# SimpleSimon.net
KiCad netlist of a schematic drawn in EAGLE
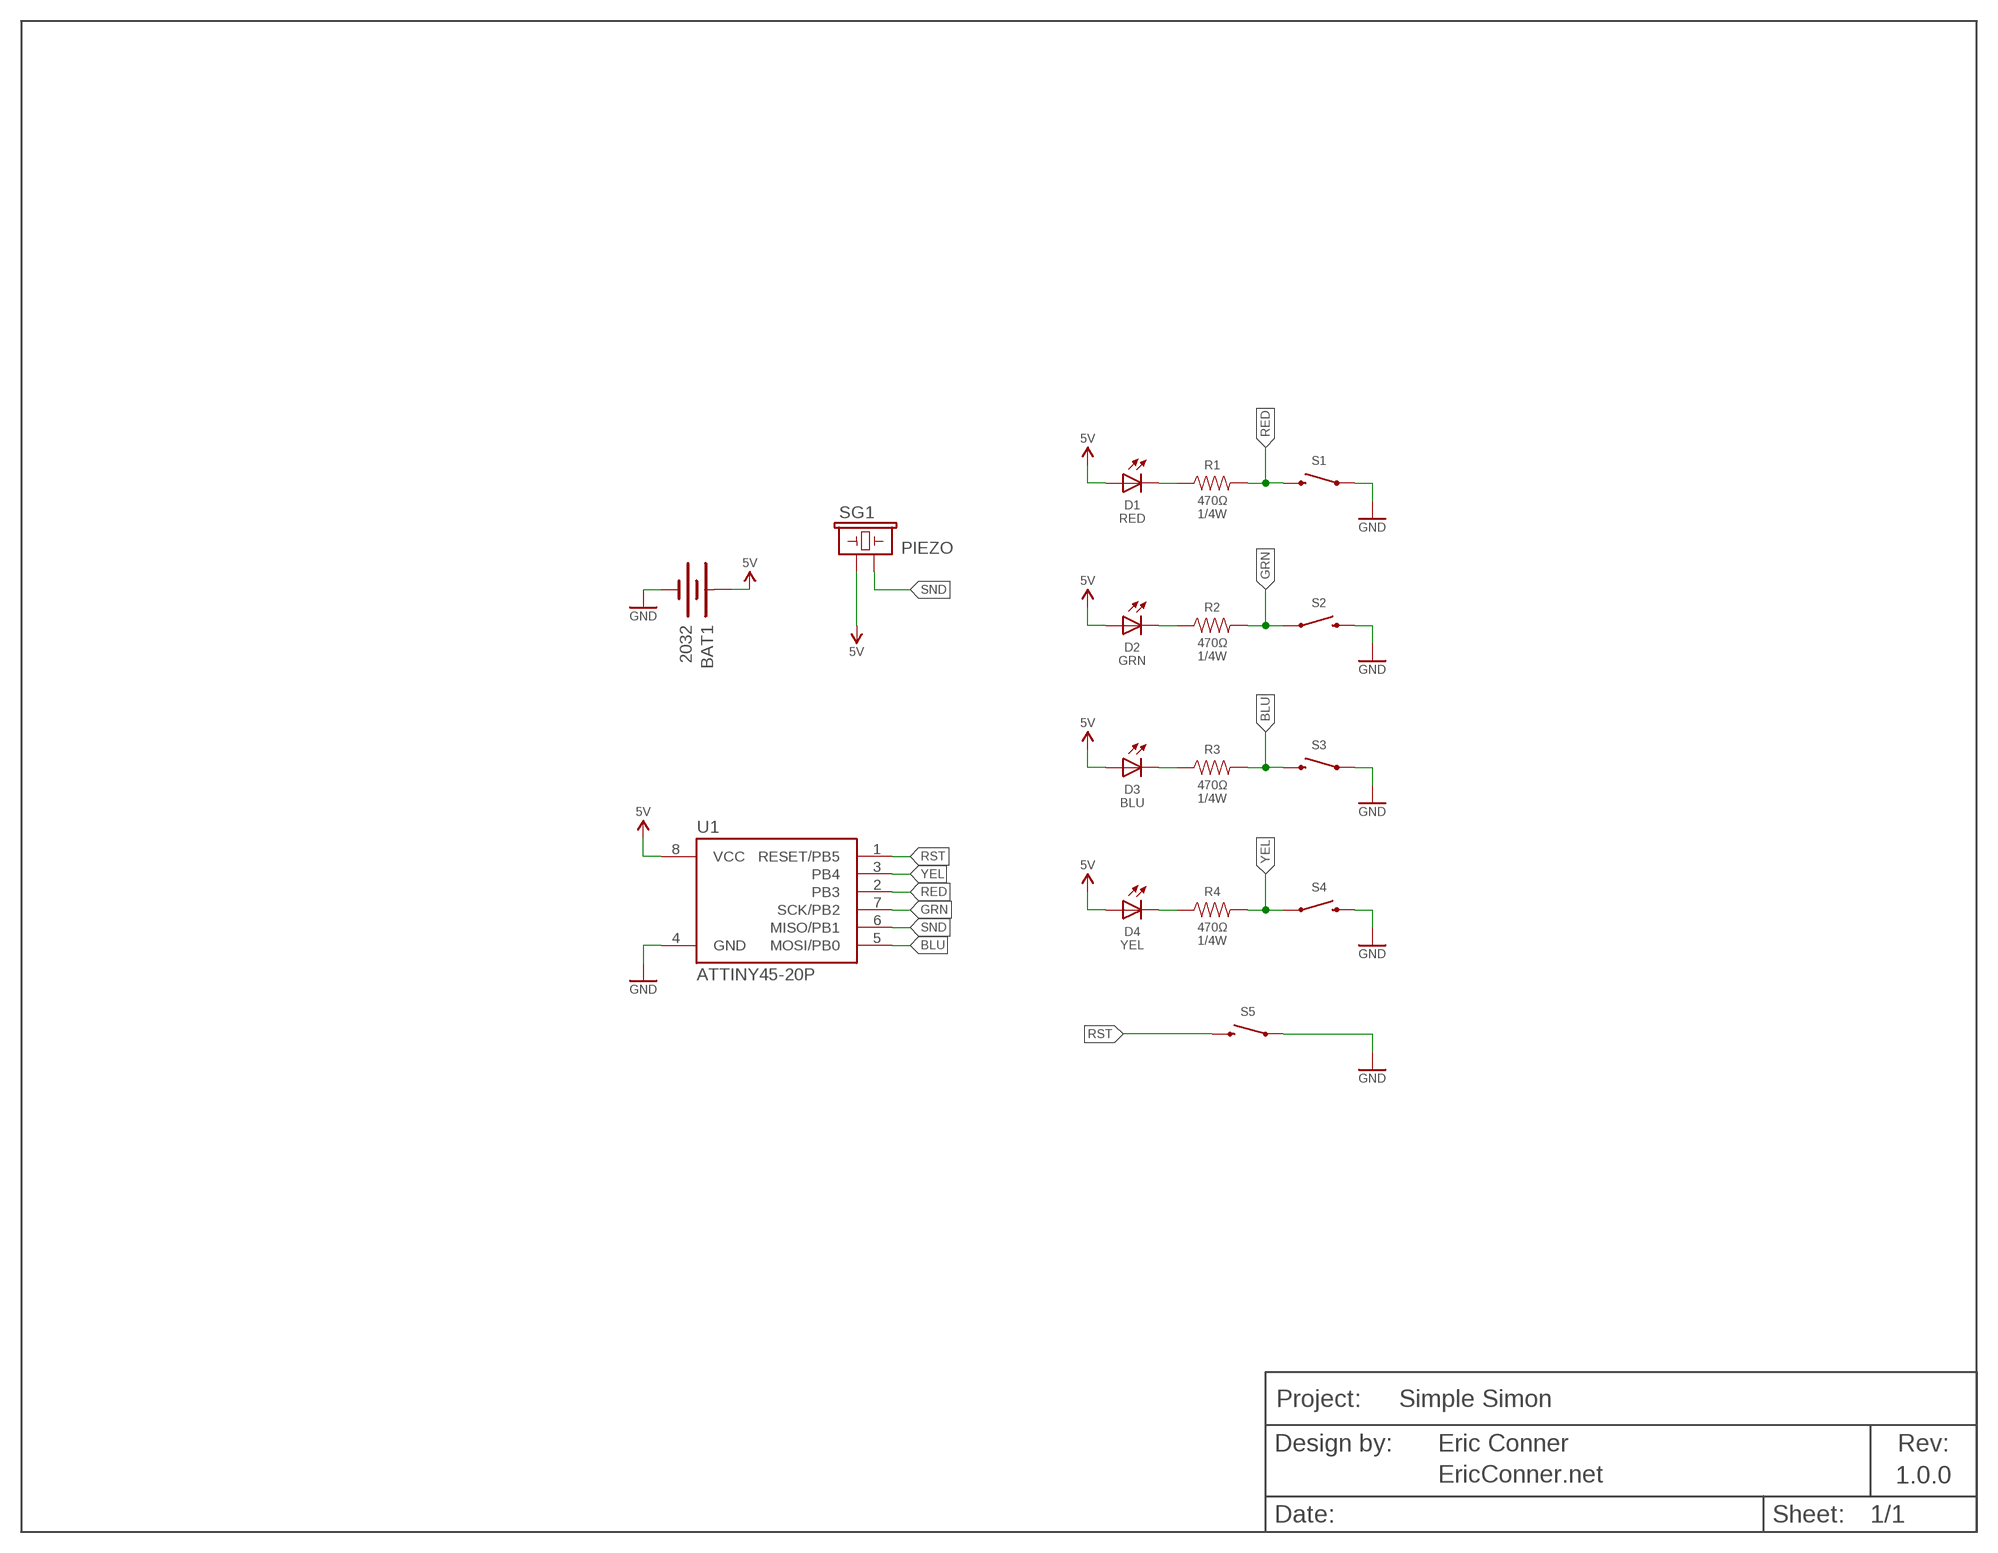
[diagram p0: schematic, sheet 1]

(export (version "E")
  (design (tool "Eeschema 10.0.6"))
  (components
    (comp (ref "BAT1")
      (value "2032")
      (footprint "eagle-import:BAT-2032")
      (libsource (lib "eagle-import") (part "BATTERY2032"))
    )
    (comp (ref "BORDER1")
      (value "BORDER_LETTER-MINIMAL")
      (footprint "eagle-import:MINIMAL_LOGO")
      (fields
        (field (name "PROJECT") "Simple Simon")
        (field (name "DESIGNER") "Eric Conner")
        (field (name "VERSION") "1.0.0")
        (field (name "WEBSITE") "EricConner.net")
        (field (name "PROJECT_1") "Simple Simon")
      )
      (libsource (lib "eagle-import") (part "BORDER_LETTER-MINIMAL"))
    )
    (comp (ref "D1")
      (value "RED")
      (footprint "eagle-import:LED5MM")
      (libsource (lib "eagle-import") (part "LED5MM"))
    )
    (comp (ref "D2")
      (value "GRN")
      (footprint "eagle-import:LED5MM")
      (libsource (lib "eagle-import") (part "LED5MM"))
    )
    (comp (ref "D3")
      (value "BLU")
      (footprint "eagle-import:LED5MM")
      (libsource (lib "eagle-import") (part "LED5MM"))
    )
    (comp (ref "D4")
      (value "YEL")
      (footprint "eagle-import:LED5MM")
      (libsource (lib "eagle-import") (part "LED5MM"))
    )
    (comp (ref "R1")
      (value "470Ω")
      (footprint "eagle-import:1_4R")
      (fields (field (name "ATTRIBUTE") "1/4W") (field (name "DIGIKEY") "CF14JT470RCT-ND"))
      (libsource (lib "eagle-import") (part "RESISTOR1/4W"))
    )
    (comp (ref "R2")
      (value "470Ω")
      (footprint "eagle-import:1_4R")
      (fields (field (name "ATTRIBUTE") "1/4W") (field (name "DIGIKEY") "CF14JT470RCT-ND"))
      (libsource (lib "eagle-import") (part "RESISTOR1/4W"))
    )
    (comp (ref "R3")
      (value "470Ω")
      (footprint "eagle-import:1_4R")
      (fields (field (name "ATTRIBUTE") "1/4W") (field (name "DIGIKEY") "CF14JT470RCT-ND"))
      (libsource (lib "eagle-import") (part "RESISTOR1/4W"))
    )
    (comp (ref "R4")
      (value "470Ω")
      (footprint "eagle-import:1_4R")
      (fields (field (name "ATTRIBUTE") "1/4W") (field (name "DIGIKEY") "CF14JT470RCT-ND"))
      (libsource (lib "eagle-import") (part "RESISTOR1/4W"))
    )
    (comp (ref "S1")
      (value "SWITCH-MOMENTARY-2PTH")
      (footprint "eagle-import:TACTILE-PTH")
      (libsource (lib "eagle-import") (part "SWITCH-MOMENTARY-2PTH"))
    )
    (comp (ref "S2")
      (value "SWITCH-MOMENTARY-2PTH")
      (footprint "eagle-import:TACTILE-PTH")
      (libsource (lib "eagle-import") (part "SWITCH-MOMENTARY-2PTH"))
    )
    (comp (ref "S3")
      (value "SWITCH-MOMENTARY-2PTH")
      (footprint "eagle-import:TACTILE-PTH")
      (libsource (lib "eagle-import") (part "SWITCH-MOMENTARY-2PTH"))
    )
    (comp (ref "S4")
      (value "SWITCH-MOMENTARY-2PTH")
      (footprint "eagle-import:TACTILE-PTH")
      (libsource (lib "eagle-import") (part "SWITCH-MOMENTARY-2PTH"))
    )
    (comp (ref "S5")
      (value "SWITCH-MOMENTARY-2PTH")
      (footprint "eagle-import:TACTILE-PTH")
      (libsource (lib "eagle-import") (part "SWITCH-MOMENTARY-2PTH"))
    )
    (comp (ref "SG1")
      (value "PIEZO")
      (footprint "eagle-import:BUZZER-12MM")
      (libsource (lib "eagle-import") (part "BUZZERPTH"))
    )
    (comp (ref "U1")
      (value "ATTINY45-20P")
      (footprint "eagle-import:PDIP08_300MIL")
      (libsource (lib "eagle-import") (part "ATTINY45P-20"))
    )
  )
  (nets
    (net (code "1") (name "5V") (class "Default")
      (node (ref "BAT1") (pin "+") (pinfunction "+_+") (pintype "power_in"))
      (node (ref "D1") (pin "A") (pinfunction "A_A") (pintype "passive"))
      (node (ref "D2") (pin "A") (pinfunction "A_A") (pintype "passive"))
      (node (ref "D3") (pin "A") (pinfunction "A_A") (pintype "passive"))
      (node (ref "D4") (pin "A") (pinfunction "A_A") (pintype "passive"))
      (node (ref "SG1") (pin "+") (pinfunction "1_+") (pintype "passive"))
      (node (ref "U1") (pin "8") (pinfunction "VCC_8") (pintype "power_in"))
    )
    (net (code "2") (name "BLU") (class "Default")
      (node (ref "R3") (pin "P$2") (pinfunction "2_P$2") (pintype "passive"))
      (node (ref "S3") (pin "3") (pinfunction "2_3") (pintype "passive"))
      (node (ref "U1") (pin "5") (pinfunction "MOSI/PB0_5") (pintype "bidirectional"))
    )
    (net (code "3") (name "GND") (class "Default")
      (node (ref "BAT1") (pin "-") (pinfunction "-_-") (pintype "power_in"))
      (node (ref "S1") (pin "1") (pinfunction "1_1") (pintype "passive"))
      (node (ref "S2") (pin "3") (pinfunction "2_3") (pintype "passive"))
      (node (ref "S3") (pin "1") (pinfunction "1_1") (pintype "passive"))
      (node (ref "S4") (pin "3") (pinfunction "2_3") (pintype "passive"))
      (node (ref "S5") (pin "1") (pinfunction "1_1") (pintype "passive"))
      (node (ref "U1") (pin "4") (pinfunction "GND_4") (pintype "power_in"))
    )
    (net (code "4") (name "GRN") (class "Default")
      (node (ref "R2") (pin "P$2") (pinfunction "2_P$2") (pintype "passive"))
      (node (ref "S2") (pin "1") (pinfunction "1_1") (pintype "passive"))
      (node (ref "U1") (pin "7") (pinfunction "SCK/PB2_7") (pintype "bidirectional"))
    )
    (net (code "5") (name "Net-(D1-C)") (class "Default")
      (node (ref "D1") (pin "K") (pinfunction "C_K") (pintype "passive"))
      (node (ref "R1") (pin "P$1") (pinfunction "1_P$1") (pintype "passive"))
    )
    (net (code "6") (name "Net-(D2-C)") (class "Default")
      (node (ref "D2") (pin "K") (pinfunction "C_K") (pintype "passive"))
      (node (ref "R2") (pin "P$1") (pinfunction "1_P$1") (pintype "passive"))
    )
    (net (code "7") (name "Net-(D3-C)") (class "Default")
      (node (ref "D3") (pin "K") (pinfunction "C_K") (pintype "passive"))
      (node (ref "R3") (pin "P$1") (pinfunction "1_P$1") (pintype "passive"))
    )
    (net (code "8") (name "Net-(D4-C)") (class "Default")
      (node (ref "D4") (pin "K") (pinfunction "C_K") (pintype "passive"))
      (node (ref "R4") (pin "P$1") (pinfunction "1_P$1") (pintype "passive"))
    )
    (net (code "9") (name "RED") (class "Default")
      (node (ref "R1") (pin "P$2") (pinfunction "2_P$2") (pintype "passive"))
      (node (ref "S1") (pin "3") (pinfunction "2_3") (pintype "passive"))
      (node (ref "U1") (pin "2") (pinfunction "PB3_2") (pintype "bidirectional"))
    )
    (net (code "10") (name "RST") (class "Default")
      (node (ref "S5") (pin "3") (pinfunction "2_3") (pintype "passive"))
      (node (ref "U1") (pin "1") (pinfunction "RESET/PB5_1") (pintype "bidirectional"))
    )
    (net (code "11") (name "SND") (class "Default")
      (node (ref "SG1") (pin "-") (pinfunction "2_-") (pintype "passive"))
      (node (ref "U1") (pin "6") (pinfunction "MISO/PB1_6") (pintype "bidirectional"))
    )
    (net (code "12") (name "YEL") (class "Default")
      (node (ref "R4") (pin "P$2") (pinfunction "2_P$2") (pintype "passive"))
      (node (ref "S4") (pin "1") (pinfunction "1_1") (pintype "passive"))
      (node (ref "U1") (pin "3") (pinfunction "PB4_3") (pintype "bidirectional"))
    )
  )
)
